# powersubpanel.net
KiCad netlist of a schematic drawn in EAGLE
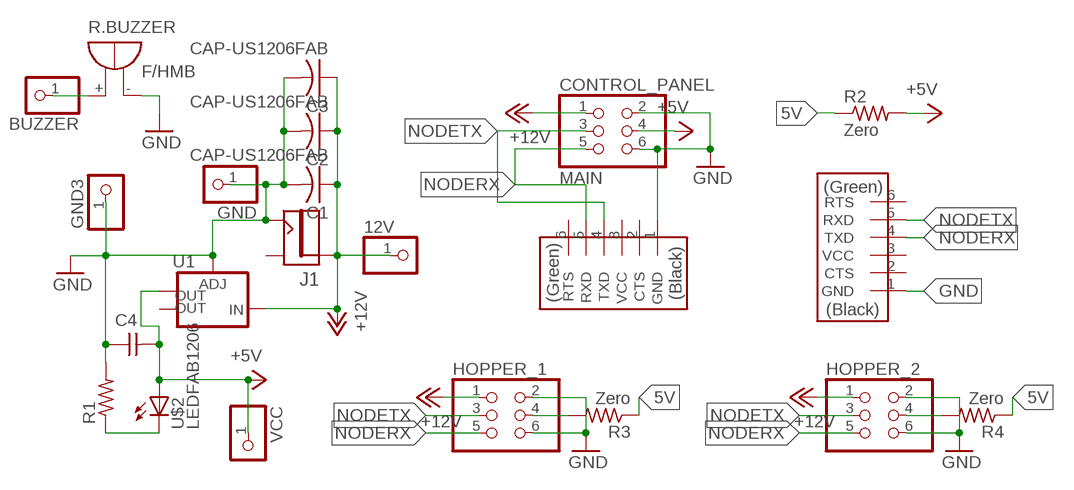
[diagram p0: schematic, sheet 1]

(export (version "E")
  (design (tool "Eeschema 10.0.6"))
  (components
    (comp (ref "12V")
      (value "PINHD-1X1")
      (footprint "eagle-import:1X01")
      (libsource (lib "eagle-import") (part "PINHD-1X1"))
    )
    (comp (ref "BUZZER")
      (value "PINHD-1X1")
      (footprint "eagle-import:1X01")
      (libsource (lib "eagle-import") (part "PINHD-1X1"))
    )
    (comp (ref "C1")
      (value "CAP-US1206FAB")
      (footprint "eagle-import:C1206FAB")
      (libsource (lib "eagle-import") (part "CAP-US1206FAB"))
    )
    (comp (ref "C2")
      (value "CAP-US1206FAB")
      (footprint "eagle-import:C1206FAB")
      (libsource (lib "eagle-import") (part "CAP-US1206FAB"))
    )
    (comp (ref "C3")
      (value "CAP-US1206FAB")
      (footprint "eagle-import:C1206FAB")
      (libsource (lib "eagle-import") (part "CAP-US1206FAB"))
    )
    (comp (ref "C4")
      (value "CAP-UNPOLARIZEDFAB")
      (footprint "eagle-import:C1206FAB")
      (libsource (lib "eagle-import") (part "CAP-UNPOLARIZEDFAB"))
    )
    (comp (ref "CONTROL_PANEL")
      (value "MAIN")
      (footprint "eagle-import:2X03SMD")
      (libsource (lib "eagle-import") (part "PINHD-2X3-SMD"))
    )
    (comp (ref "FORCONTROLLER")
      (value "FTDI-SMD-HEADER")
      (footprint "eagle-import:1X06SMD")
      (libsource (lib "eagle-import") (part "FTDI-SMD-HEADER"))
    )
    (comp (ref "FORHOPPER")
      (value "FTDI-SMD-HEADER")
      (footprint "eagle-import:1X06SMD")
      (libsource (lib "eagle-import") (part "FTDI-SMD-HEADER"))
    )
    (comp (ref "GND")
      (value "PINHD-1X1")
      (footprint "eagle-import:1X01")
      (libsource (lib "eagle-import") (part "PINHD-1X1"))
    )
    (comp (ref "GND3")
      (value "PINHD-1X1")
      (footprint "eagle-import:1X01")
      (libsource (lib "eagle-import") (part "PINHD-1X1"))
    )
    (comp (ref "HOPPER_1")
      (value "PINHD-2X3-SMD")
      (footprint "eagle-import:2X03SMD")
      (libsource (lib "eagle-import") (part "PINHD-2X3-SMD"))
    )
    (comp (ref "HOPPER_2")
      (value "PINHD-2X3-SMD")
      (footprint "eagle-import:2X03SMD")
      (libsource (lib "eagle-import") (part "PINHD-2X3-SMD"))
    )
    (comp (ref "J1")
      (value "JACK2.1MM")
      (footprint "eagle-import:JACK_2.1MM")
      (libsource (lib "eagle-import") (part "JACK2.1MM"))
    )
    (comp (ref "R.BUZZER")
      (value "F/HMB")
      (footprint "eagle-import:F_HMB")
      (libsource (lib "eagle-import") (part "F/HMB"))
    )
    (comp (ref "R1")
      (value "RES-US1206FAB")
      (footprint "eagle-import:R1206FAB")
      (libsource (lib "eagle-import") (part "RES-US1206FAB"))
    )
    (comp (ref "R2")
      (value "Zero")
      (footprint "eagle-import:R1206FAB")
      (libsource (lib "eagle-import") (part "RES-US1206FAB"))
    )
    (comp (ref "R3")
      (value "Zero")
      (footprint "eagle-import:R1206FAB")
      (libsource (lib "eagle-import") (part "RES-US1206FAB"))
    )
    (comp (ref "R4")
      (value "Zero")
      (footprint "eagle-import:R1206FAB")
      (libsource (lib "eagle-import") (part "RES-US1206FAB"))
    )
    (comp (ref "U$2")
      (value "LEDFAB1206")
      (footprint "eagle-import:LED1206FAB")
      (libsource (lib "eagle-import") (part "LEDFAB1206"))
    )
    (comp (ref "U1")
      (value "V_REG_LM1117SOT223")
      (footprint "eagle-import:SOT223")
      (libsource (lib "eagle-import") (part "V_REG_LM1117SOT223"))
    )
    (comp (ref "VCC")
      (value "PINHD-1X1")
      (footprint "eagle-import:1X01")
      (libsource (lib "eagle-import") (part "PINHD-1X1"))
    )
  )
  (nets
    (net (code "1") (name "+5V") (class "Default")
      (node (ref "C4") (pin "2") (pinfunction "2_2") (pintype "passive"))
      (node (ref "CONTROL_PANEL") (pin "4") (pinfunction "4_4") (pintype "passive"))
      (node (ref "R2") (pin "2") (pinfunction "2_2") (pintype "passive"))
      (node (ref "U$2") (pin "1") (pinfunction "A_1") (pintype "passive"))
      (node (ref "U1") (pin "4") (pinfunction "OUT_4") (pintype "output"))
      (node (ref "VCC") (pin "1") (pinfunction "1_1") (pintype "passive"))
    )
    (net (code "2") (name "+12V") (class "Default")
      (node (ref "12V") (pin "1") (pinfunction "1_1") (pintype "passive"))
      (node (ref "C1") (pin "1") (pinfunction "1_1") (pintype "passive"))
      (node (ref "C2") (pin "1") (pinfunction "1_1") (pintype "passive"))
      (node (ref "C3") (pin "1") (pinfunction "1_1") (pintype "passive"))
      (node (ref "CONTROL_PANEL") (pin "1") (pinfunction "1_1") (pintype "passive"))
      (node (ref "HOPPER_1") (pin "1") (pinfunction "1_1") (pintype "passive"))
      (node (ref "HOPPER_2") (pin "1") (pinfunction "1_1") (pintype "passive"))
      (node (ref "J1") (pin "PIN") (pinfunction "PIN_PIN") (pintype "bidirectional"))
      (node (ref "U1") (pin "3") (pinfunction "IN_3") (pintype "input"))
    )
    (net (code "3") (name "5V") (class "Default")
      (node (ref "R2") (pin "1") (pinfunction "1_1") (pintype "passive"))
      (node (ref "R3") (pin "1") (pinfunction "1_1") (pintype "passive"))
      (node (ref "R4") (pin "1") (pinfunction "1_1") (pintype "passive"))
    )
    (net (code "4") (name "GND") (class "Default")
      (node (ref "C1") (pin "2") (pinfunction "2_2") (pintype "passive"))
      (node (ref "C2") (pin "2") (pinfunction "2_2") (pintype "passive"))
      (node (ref "C3") (pin "2") (pinfunction "2_2") (pintype "passive"))
      (node (ref "C4") (pin "1") (pinfunction "1_1") (pintype "passive"))
      (node (ref "CONTROL_PANEL") (pin "2") (pinfunction "2_2") (pintype "passive"))
      (node (ref "CONTROL_PANEL") (pin "6") (pinfunction "6_6") (pintype "passive"))
      (node (ref "FORCONTROLLER") (pin "1") (pinfunction "GND_1") (pintype "bidirectional"))
      (node (ref "FORHOPPER") (pin "1") (pinfunction "GND_1") (pintype "bidirectional"))
      (node (ref "GND") (pin "1") (pinfunction "1_1") (pintype "passive"))
      (node (ref "GND3") (pin "1") (pinfunction "1_1") (pintype "passive"))
      (node (ref "HOPPER_1") (pin "2") (pinfunction "2_2") (pintype "passive"))
      (node (ref "HOPPER_1") (pin "6") (pinfunction "6_6") (pintype "passive"))
      (node (ref "HOPPER_2") (pin "2") (pinfunction "2_2") (pintype "passive"))
      (node (ref "HOPPER_2") (pin "6") (pinfunction "6_6") (pintype "passive"))
      (node (ref "J1") (pin "CONTACT") (pinfunction "CONTACT_CONTACT") (pintype "bidirectional"))
      (node (ref "R.BUZZER") (pin "-") (pinfunction "-_-") (pintype "passive"))
      (node (ref "R1") (pin "2") (pinfunction "2_2") (pintype "passive"))
      (node (ref "U1") (pin "1") (pinfunction "ADJ_1") (pintype "input"))
    )
    (net (code "5") (name "NODERX") (class "Default")
      (node (ref "CONTROL_PANEL") (pin "5") (pinfunction "5_5") (pintype "passive"))
      (node (ref "FORCONTROLLER") (pin "5") (pinfunction "RXD_5") (pintype "bidirectional"))
      (node (ref "FORHOPPER") (pin "4") (pinfunction "TXD_4") (pintype "bidirectional"))
      (node (ref "HOPPER_1") (pin "5") (pinfunction "5_5") (pintype "passive"))
      (node (ref "HOPPER_2") (pin "5") (pinfunction "5_5") (pintype "passive"))
    )
    (net (code "6") (name "NODETX") (class "Default")
      (node (ref "CONTROL_PANEL") (pin "3") (pinfunction "3_3") (pintype "passive"))
      (node (ref "FORCONTROLLER") (pin "4") (pinfunction "TXD_4") (pintype "bidirectional"))
      (node (ref "FORHOPPER") (pin "5") (pinfunction "RXD_5") (pintype "bidirectional"))
      (node (ref "HOPPER_1") (pin "3") (pinfunction "3_3") (pintype "passive"))
      (node (ref "HOPPER_2") (pin "3") (pinfunction "3_3") (pintype "passive"))
    )
    (net (code "7") (name "Net-(BUZZER-Pad1)") (class "Default")
      (node (ref "BUZZER") (pin "1") (pinfunction "1_1") (pintype "passive"))
      (node (ref "R.BUZZER") (pin "+") (pinfunction "+_+") (pintype "passive"))
    )
    (net (code "8") (name "Net-(HOPPER_1-Pad4)") (class "Default")
      (node (ref "HOPPER_1") (pin "4") (pinfunction "4_4") (pintype "passive"))
      (node (ref "R3") (pin "2") (pinfunction "2_2") (pintype "passive"))
    )
    (net (code "9") (name "Net-(HOPPER_2-Pad4)") (class "Default")
      (node (ref "HOPPER_2") (pin "4") (pinfunction "4_4") (pintype "passive"))
      (node (ref "R4") (pin "2") (pinfunction "2_2") (pintype "passive"))
    )
    (net (code "10") (name "Net-(U$2-C)") (class "Default")
      (node (ref "R1") (pin "1") (pinfunction "1_1") (pintype "passive"))
      (node (ref "U$2") (pin "2") (pinfunction "C_2") (pintype "passive"))
    )
    (net (code "11") (name "unconnected-(FORCONTROLLER-CTS-Pad2)") (class "Default")
      (node (ref "FORCONTROLLER") (pin "2") (pinfunction "CTS_2") (pintype "bidirectional"))
    )
    (net (code "12") (name "unconnected-(FORCONTROLLER-RTS-Pad6)") (class "Default")
      (node (ref "FORCONTROLLER") (pin "6") (pinfunction "RTS_6") (pintype "bidirectional"))
    )
    (net (code "13") (name "unconnected-(FORCONTROLLER-VCC-Pad3)") (class "Default")
      (node (ref "FORCONTROLLER") (pin "3") (pinfunction "VCC_3") (pintype "bidirectional"))
    )
    (net (code "14") (name "unconnected-(FORHOPPER-CTS-Pad2)") (class "Default")
      (node (ref "FORHOPPER") (pin "2") (pinfunction "CTS_2") (pintype "bidirectional"))
    )
    (net (code "15") (name "unconnected-(FORHOPPER-RTS-Pad6)") (class "Default")
      (node (ref "FORHOPPER") (pin "6") (pinfunction "RTS_6") (pintype "bidirectional"))
    )
    (net (code "16") (name "unconnected-(FORHOPPER-VCC-Pad3)") (class "Default")
      (node (ref "FORHOPPER") (pin "3") (pinfunction "VCC_3") (pintype "bidirectional"))
    )
    (net (code "17") (name "unconnected-(J1-PadSHUNT)") (class "Default")
      (node (ref "J1") (pin "SHUNT") (pinfunction "SHUNT_SHUNT") (pintype "bidirectional"))
    )
    (net (code "18") (name "unconnected-(U1-OUT-Pad2)") (class "Default")
      (node (ref "U1") (pin "2") (pinfunction "OUT_2") (pintype "output"))
    )
  )
)
